# b295_rev0.net
KiCad netlist of a schematic drawn in EAGLE
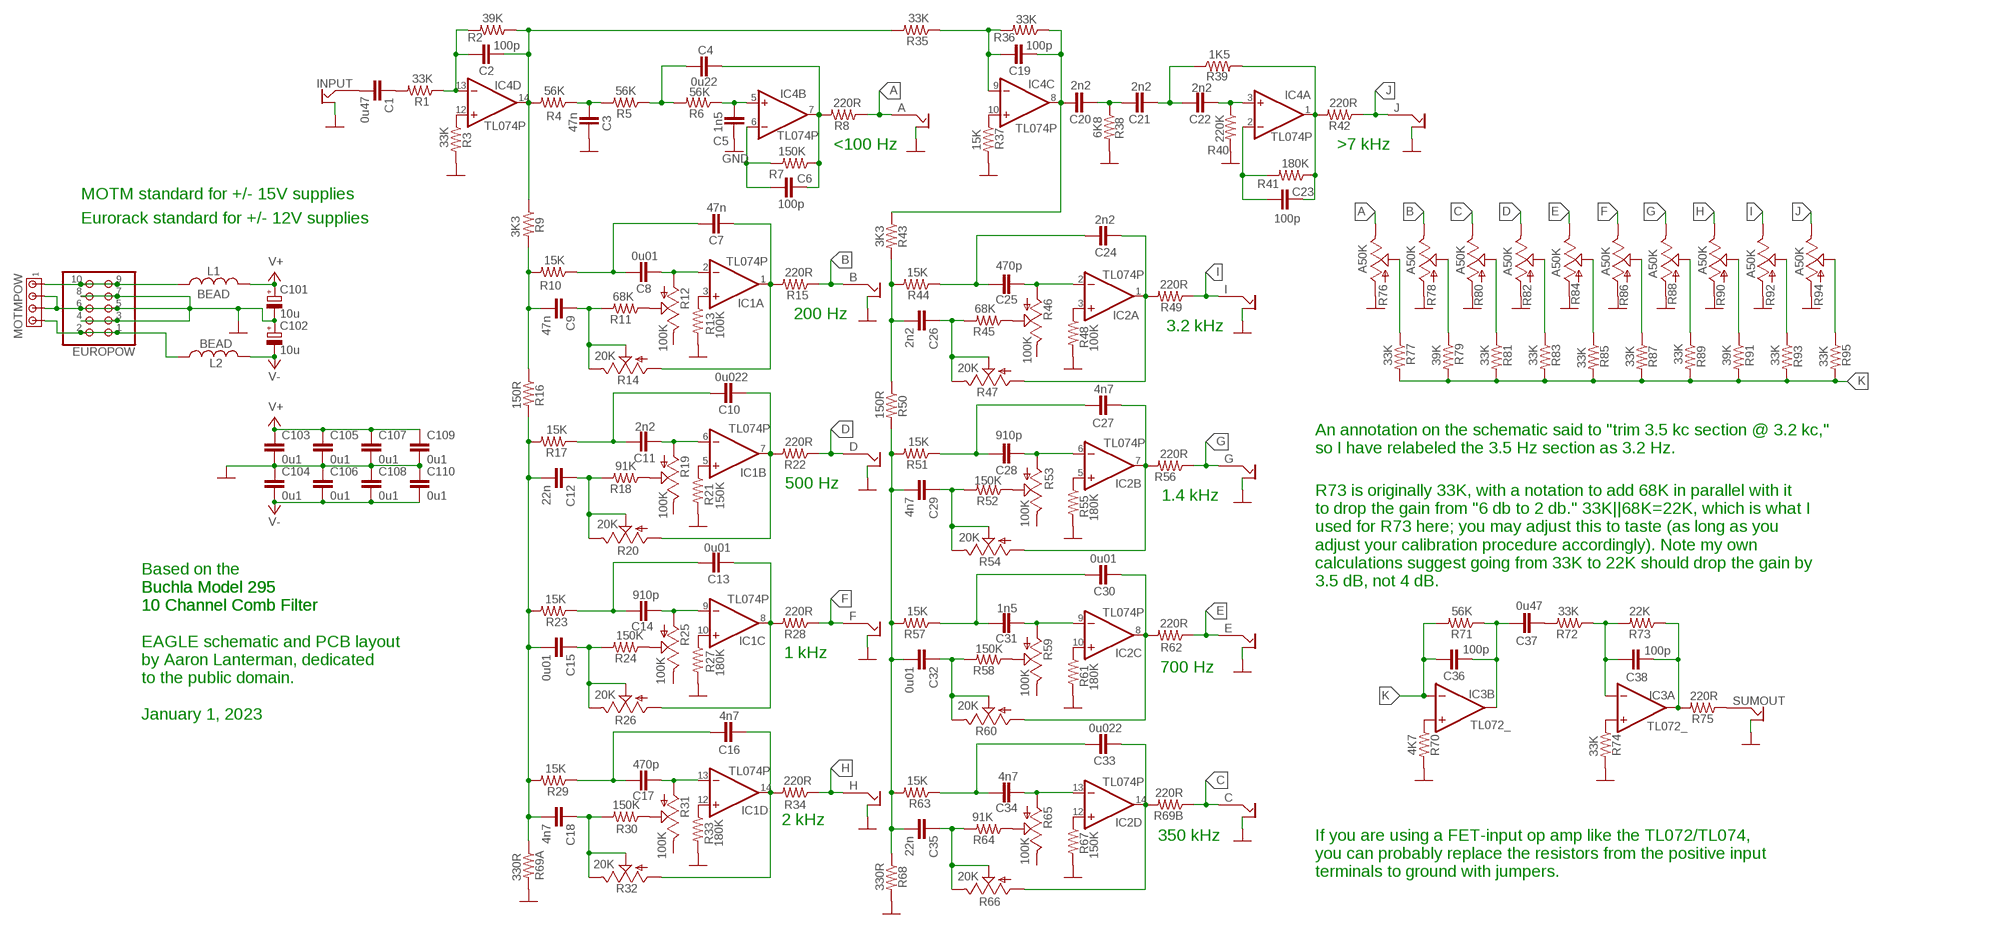
[diagram p0: schematic, sheet 1]

(export (version "E")
  (design (tool "Eeschema 10.0.6"))
  (components
    (comp (ref "A")
      (value "OFFBOARD2JACKALT_AARON")
      (footprint "eagle-import:OFFBOARD2JACKALT")
      (libsource (lib "eagle-import") (part "OFFBOARD2JACKALT_AARON"))
    )
    (comp (ref "B")
      (value "OFFBOARD2JACKALT_AARON")
      (footprint "eagle-import:OFFBOARD2JACKALT")
      (libsource (lib "eagle-import") (part "OFFBOARD2JACKALT_AARON"))
    )
    (comp (ref "C")
      (value "OFFBOARD2JACKALT_AARON")
      (footprint "eagle-import:OFFBOARD2JACKALT")
      (libsource (lib "eagle-import") (part "OFFBOARD2JACKALT_AARON"))
    )
    (comp (ref "C1")
      (value "0u47")
      (footprint "eagle-import:C050-025X075-AARON")
      (libsource (lib "eagle-import") (part "C-EU050-025X075-AARON"))
    )
    (comp (ref "C2")
      (value "100p")
      (footprint "eagle-import:C050-025X075-AARON")
      (libsource (lib "eagle-import") (part "C-EU050-025X075-AARON"))
    )
    (comp (ref "C3")
      (value "47n")
      (footprint "eagle-import:C050-025X075-AARON")
      (libsource (lib "eagle-import") (part "C-EU050-025X075-AARON"))
    )
    (comp (ref "C4")
      (value "0u22")
      (footprint "eagle-import:C050-025X075-AARON")
      (libsource (lib "eagle-import") (part "C-EU050-025X075-AARON"))
    )
    (comp (ref "C5")
      (value "1n5")
      (footprint "eagle-import:C050-025X075-AARON")
      (libsource (lib "eagle-import") (part "C-EU050-025X075-AARON"))
    )
    (comp (ref "C6")
      (value "100p")
      (footprint "eagle-import:C050-025X075-AARON")
      (libsource (lib "eagle-import") (part "C-EU050-025X075-AARON"))
    )
    (comp (ref "C7")
      (value "47n")
      (footprint "eagle-import:C050-025X075-AARON")
      (libsource (lib "eagle-import") (part "C-EU050-025X075-AARON"))
    )
    (comp (ref "C8")
      (value "0u01")
      (footprint "eagle-import:C050-025X075-AARON")
      (libsource (lib "eagle-import") (part "C-EU050-025X075-AARON"))
    )
    (comp (ref "C9")
      (value "47n")
      (footprint "eagle-import:C050-025X075-AARON")
      (libsource (lib "eagle-import") (part "C-EU050-025X075-AARON"))
    )
    (comp (ref "C10")
      (value "0u022")
      (footprint "eagle-import:C050-025X075-AARON")
      (libsource (lib "eagle-import") (part "C-EU050-025X075-AARON"))
    )
    (comp (ref "C11")
      (value "2n2")
      (footprint "eagle-import:C050-025X075-AARON")
      (libsource (lib "eagle-import") (part "C-EU050-025X075-AARON"))
    )
    (comp (ref "C12")
      (value "22n")
      (footprint "eagle-import:C050-025X075-AARON")
      (libsource (lib "eagle-import") (part "C-EU050-025X075-AARON"))
    )
    (comp (ref "C13")
      (value "0u01")
      (footprint "eagle-import:C050-025X075-AARON")
      (libsource (lib "eagle-import") (part "C-EU050-025X075-AARON"))
    )
    (comp (ref "C14")
      (value "910p")
      (footprint "eagle-import:C050-025X075-AARON")
      (libsource (lib "eagle-import") (part "C-EU050-025X075-AARON"))
    )
    (comp (ref "C15")
      (value "0u01")
      (footprint "eagle-import:C050-025X075-AARON")
      (libsource (lib "eagle-import") (part "C-EU050-025X075-AARON"))
    )
    (comp (ref "C16")
      (value "4n7")
      (footprint "eagle-import:C050-025X075-AARON")
      (libsource (lib "eagle-import") (part "C-EU050-025X075-AARON"))
    )
    (comp (ref "C17")
      (value "470p")
      (footprint "eagle-import:C050-025X075-AARON")
      (libsource (lib "eagle-import") (part "C-EU050-025X075-AARON"))
    )
    (comp (ref "C18")
      (value "4n7")
      (footprint "eagle-import:C050-025X075-AARON")
      (libsource (lib "eagle-import") (part "C-EU050-025X075-AARON"))
    )
    (comp (ref "C19")
      (value "100p")
      (footprint "eagle-import:C050-025X075-AARON")
      (libsource (lib "eagle-import") (part "C-EU050-025X075-AARON"))
    )
    (comp (ref "C20")
      (value "2n2")
      (footprint "eagle-import:C050-025X075-AARON")
      (libsource (lib "eagle-import") (part "C-EU050-025X075-AARON"))
    )
    (comp (ref "C21")
      (value "2n2")
      (footprint "eagle-import:C050-025X075-AARON")
      (libsource (lib "eagle-import") (part "C-EU050-025X075-AARON"))
    )
    (comp (ref "C22")
      (value "2n2")
      (footprint "eagle-import:C050-025X075-AARON")
      (libsource (lib "eagle-import") (part "C-EU050-025X075-AARON"))
    )
    (comp (ref "C23")
      (value "100p")
      (footprint "eagle-import:C050-025X075-AARON")
      (libsource (lib "eagle-import") (part "C-EU050-025X075-AARON"))
    )
    (comp (ref "C24")
      (value "2n2")
      (footprint "eagle-import:C050-025X075-AARON")
      (libsource (lib "eagle-import") (part "C-EU050-025X075-AARON"))
    )
    (comp (ref "C25")
      (value "470p")
      (footprint "eagle-import:C050-025X075-AARON")
      (libsource (lib "eagle-import") (part "C-EU050-025X075-AARON"))
    )
    (comp (ref "C26")
      (value "2n2")
      (footprint "eagle-import:C050-025X075-AARON")
      (libsource (lib "eagle-import") (part "C-EU050-025X075-AARON"))
    )
    (comp (ref "C27")
      (value "4n7")
      (footprint "eagle-import:C050-025X075-AARON")
      (libsource (lib "eagle-import") (part "C-EU050-025X075-AARON"))
    )
    (comp (ref "C28")
      (value "910p")
      (footprint "eagle-import:C050-025X075-AARON")
      (libsource (lib "eagle-import") (part "C-EU050-025X075-AARON"))
    )
    (comp (ref "C29")
      (value "4n7")
      (footprint "eagle-import:C050-025X075-AARON")
      (libsource (lib "eagle-import") (part "C-EU050-025X075-AARON"))
    )
    (comp (ref "C30")
      (value "0u01")
      (footprint "eagle-import:C050-025X075-AARON")
      (libsource (lib "eagle-import") (part "C-EU050-025X075-AARON"))
    )
    (comp (ref "C31")
      (value "1n5")
      (footprint "eagle-import:C050-025X075-AARON")
      (libsource (lib "eagle-import") (part "C-EU050-025X075-AARON"))
    )
    (comp (ref "C32")
      (value "0u01")
      (footprint "eagle-import:C050-025X075-AARON")
      (libsource (lib "eagle-import") (part "C-EU050-025X075-AARON"))
    )
    (comp (ref "C33")
      (value "0u022")
      (footprint "eagle-import:C050-025X075-AARON")
      (libsource (lib "eagle-import") (part "C-EU050-025X075-AARON"))
    )
    (comp (ref "C34")
      (value "4n7")
      (footprint "eagle-import:C050-025X075-AARON")
      (libsource (lib "eagle-import") (part "C-EU050-025X075-AARON"))
    )
    (comp (ref "C35")
      (value "22n")
      (footprint "eagle-import:C050-025X075-AARON")
      (libsource (lib "eagle-import") (part "C-EU050-025X075-AARON"))
    )
    (comp (ref "C36")
      (value "100p")
      (footprint "eagle-import:C050-025X075-AARON")
      (libsource (lib "eagle-import") (part "C-EU050-025X075-AARON"))
    )
    (comp (ref "C37")
      (value "0u47")
      (footprint "eagle-import:C050-025X075-AARON")
      (libsource (lib "eagle-import") (part "C-EU050-025X075-AARON"))
    )
    (comp (ref "C38")
      (value "100p")
      (footprint "eagle-import:C050-025X075-AARON")
      (libsource (lib "eagle-import") (part "C-EU050-025X075-AARON"))
    )
    (comp (ref "C101")
      (value "10u")
      (footprint "eagle-import:E1,8-4")
      (libsource (lib "eagle-import") (part "CPOL-EUE1.8-4"))
    )
    (comp (ref "C102")
      (value "10u")
      (footprint "eagle-import:E1,8-4")
      (libsource (lib "eagle-import") (part "CPOL-EUE1.8-4"))
    )
    (comp (ref "C103")
      (value "0u1")
      (footprint "eagle-import:C050-025X075-AARON")
      (libsource (lib "eagle-import") (part "C-EU050-025X075-AARON"))
    )
    (comp (ref "C104")
      (value "0u1")
      (footprint "eagle-import:C050-025X075-AARON")
      (libsource (lib "eagle-import") (part "C-EU050-025X075-AARON"))
    )
    (comp (ref "C105")
      (value "0u1")
      (footprint "eagle-import:C050-025X075-AARON")
      (libsource (lib "eagle-import") (part "C-EU050-025X075-AARON"))
    )
    (comp (ref "C106")
      (value "0u1")
      (footprint "eagle-import:C050-025X075-AARON")
      (libsource (lib "eagle-import") (part "C-EU050-025X075-AARON"))
    )
    (comp (ref "C107")
      (value "0u1")
      (footprint "eagle-import:C050-025X075-AARON")
      (libsource (lib "eagle-import") (part "C-EU050-025X075-AARON"))
    )
    (comp (ref "C108")
      (value "0u1")
      (footprint "eagle-import:C050-025X075-AARON")
      (libsource (lib "eagle-import") (part "C-EU050-025X075-AARON"))
    )
    (comp (ref "C109")
      (value "0u1")
      (footprint "eagle-import:C050-025X075-AARON")
      (libsource (lib "eagle-import") (part "C-EU050-025X075-AARON"))
    )
    (comp (ref "C110")
      (value "0u1")
      (footprint "eagle-import:C050-025X075-AARON")
      (libsource (lib "eagle-import") (part "C-EU050-025X075-AARON"))
    )
    (comp (ref "D")
      (value "OFFBOARD2JACKALT_AARON")
      (footprint "eagle-import:OFFBOARD2JACKALT")
      (libsource (lib "eagle-import") (part "OFFBOARD2JACKALT_AARON"))
    )
    (comp (ref "E")
      (value "OFFBOARD2JACKALT_AARON")
      (footprint "eagle-import:OFFBOARD2JACKALT")
      (libsource (lib "eagle-import") (part "OFFBOARD2JACKALT_AARON"))
    )
    (comp (ref "EUROPOW")
      (value "PINHD-2X5")
      (footprint "eagle-import:2X05")
      (libsource (lib "eagle-import") (part "PINHD-2X5"))
    )
    (comp (ref "F")
      (value "OFFBOARD2JACKALT_AARON")
      (footprint "eagle-import:OFFBOARD2JACKALT")
      (libsource (lib "eagle-import") (part "OFFBOARD2JACKALT_AARON"))
    )
    (comp (ref "G")
      (value "OFFBOARD2JACKALT_AARON")
      (footprint "eagle-import:OFFBOARD2JACKALT")
      (libsource (lib "eagle-import") (part "OFFBOARD2JACKALT_AARON"))
    )
    (comp (ref "H")
      (value "OFFBOARD2JACKALT_AARON")
      (footprint "eagle-import:OFFBOARD2JACKALT")
      (libsource (lib "eagle-import") (part "OFFBOARD2JACKALT_AARON"))
    )
    (comp (ref "I")
      (value "OFFBOARD2JACKALT_AARON")
      (footprint "eagle-import:OFFBOARD2JACKALT")
      (libsource (lib "eagle-import") (part "OFFBOARD2JACKALT_AARON"))
    )
    (comp (ref "IC1")
      (value "TL074P")
      (footprint "eagle-import:DIL14")
      (libsource (lib "eagle-import") (part "TL074P"))
    )
    (comp (ref "IC2")
      (value "TL074P")
      (footprint "eagle-import:DIL14")
      (libsource (lib "eagle-import") (part "TL074P"))
    )
    (comp (ref "IC3")
      (value "TL072_")
      (footprint "eagle-import:DIL08")
      (libsource (lib "eagle-import") (part "TL072_"))
    )
    (comp (ref "IC4")
      (value "TL074P")
      (footprint "eagle-import:DIL14")
      (libsource (lib "eagle-import") (part "TL074P"))
    )
    (comp (ref "INPUT")
      (value "OFFBOARD2JACKALT_AARON")
      (footprint "eagle-import:OFFBOARD2JACKALT")
      (libsource (lib "eagle-import") (part "OFFBOARD2JACKALT_AARON"))
    )
    (comp (ref "J")
      (value "OFFBOARD2JACKALT_AARON")
      (footprint "eagle-import:OFFBOARD2JACKALT")
      (libsource (lib "eagle-import") (part "OFFBOARD2JACKALT_AARON"))
    )
    (comp (ref "L1")
      (value "BEAD")
      (footprint "eagle-import:0207_10")
      (libsource (lib "eagle-import") (part "L-US0207/10"))
    )
    (comp (ref "L2")
      (value "BEAD")
      (footprint "eagle-import:0207_10")
      (libsource (lib "eagle-import") (part "L-US0207/10"))
    )
    (comp (ref "MOTMPOW")
      (value "MTA04-156")
      (footprint "eagle-import:1X4MTA")
      (libsource (lib "eagle-import") (part "MTA04-156"))
    )
    (comp (ref "R1")
      (value "33K")
      (footprint "eagle-import:0207_10")
      (libsource (lib "eagle-import") (part "R-US_0207/10"))
    )
    (comp (ref "R2")
      (value "39K")
      (footprint "eagle-import:0207_10")
      (libsource (lib "eagle-import") (part "R-US_0207/10"))
    )
    (comp (ref "R3")
      (value "33K")
      (footprint "eagle-import:0207_10")
      (libsource (lib "eagle-import") (part "R-US_0207/10"))
    )
    (comp (ref "R4")
      (value "56K")
      (footprint "eagle-import:0207_10")
      (libsource (lib "eagle-import") (part "R-US_0207/10"))
    )
    (comp (ref "R5")
      (value "56K")
      (footprint "eagle-import:0207_10")
      (libsource (lib "eagle-import") (part "R-US_0207/10"))
    )
    (comp (ref "R6")
      (value "56K")
      (footprint "eagle-import:0207_10")
      (libsource (lib "eagle-import") (part "R-US_0207/10"))
    )
    (comp (ref "R7")
      (value "150K")
      (footprint "eagle-import:0207_10")
      (libsource (lib "eagle-import") (part "R-US_0207/10"))
    )
    (comp (ref "R8")
      (value "220R")
      (footprint "eagle-import:0207_10")
      (libsource (lib "eagle-import") (part "R-US_0207/10"))
    )
    (comp (ref "R9")
      (value "3K3")
      (footprint "eagle-import:0207_10")
      (libsource (lib "eagle-import") (part "R-US_0207/10"))
    )
    (comp (ref "R10")
      (value "15K")
      (footprint "eagle-import:0207_10")
      (libsource (lib "eagle-import") (part "R-US_0207/10"))
    )
    (comp (ref "R11")
      (value "68K")
      (footprint "eagle-import:0207_10")
      (libsource (lib "eagle-import") (part "R-US_0207/10"))
    )
    (comp (ref "R12")
      (value "100K")
      (footprint "eagle-import:B64Y")
      (libsource (lib "eagle-import") (part "TRIM_US-B64Y"))
    )
    (comp (ref "R13")
      (value "100K")
      (footprint "eagle-import:0207_10")
      (libsource (lib "eagle-import") (part "R-US_0207/10"))
    )
    (comp (ref "R14")
      (value "20K")
      (footprint "eagle-import:B64Y")
      (libsource (lib "eagle-import") (part "TRIM_US-B64Y"))
    )
    (comp (ref "R15")
      (value "220R")
      (footprint "eagle-import:0207_10")
      (libsource (lib "eagle-import") (part "R-US_0207/10"))
    )
    (comp (ref "R16")
      (value "150R")
      (footprint "eagle-import:0207_10")
      (libsource (lib "eagle-import") (part "R-US_0207/10"))
    )
    (comp (ref "R17")
      (value "15K")
      (footprint "eagle-import:0207_10")
      (libsource (lib "eagle-import") (part "R-US_0207/10"))
    )
    (comp (ref "R18")
      (value "91K")
      (footprint "eagle-import:0207_10")
      (libsource (lib "eagle-import") (part "R-US_0207/10"))
    )
    (comp (ref "R19")
      (value "100K")
      (footprint "eagle-import:B64Y")
      (libsource (lib "eagle-import") (part "TRIM_US-B64Y"))
    )
    (comp (ref "R20")
      (value "20K")
      (footprint "eagle-import:B64Y")
      (libsource (lib "eagle-import") (part "TRIM_US-B64Y"))
    )
    (comp (ref "R21")
      (value "150K")
      (footprint "eagle-import:0207_10")
      (libsource (lib "eagle-import") (part "R-US_0207/10"))
    )
    (comp (ref "R22")
      (value "220R")
      (footprint "eagle-import:0207_10")
      (libsource (lib "eagle-import") (part "R-US_0207/10"))
    )
    (comp (ref "R23")
      (value "15K")
      (footprint "eagle-import:0207_10")
      (libsource (lib "eagle-import") (part "R-US_0207/10"))
    )
    (comp (ref "R24")
      (value "150K")
      (footprint "eagle-import:0207_10")
      (libsource (lib "eagle-import") (part "R-US_0207/10"))
    )
    (comp (ref "R25")
      (value "100K")
      (footprint "eagle-import:B64Y")
      (libsource (lib "eagle-import") (part "TRIM_US-B64Y"))
    )
    (comp (ref "R26")
      (value "20K")
      (footprint "eagle-import:B64Y")
      (libsource (lib "eagle-import") (part "TRIM_US-B64Y"))
    )
    (comp (ref "R27")
      (value "180K")
      (footprint "eagle-import:0207_10")
      (libsource (lib "eagle-import") (part "R-US_0207/10"))
    )
    (comp (ref "R28")
      (value "220R")
      (footprint "eagle-import:0207_10")
      (libsource (lib "eagle-import") (part "R-US_0207/10"))
    )
    (comp (ref "R29")
      (value "15K")
      (footprint "eagle-import:0207_10")
      (libsource (lib "eagle-import") (part "R-US_0207/10"))
    )
    (comp (ref "R30")
      (value "150K")
      (footprint "eagle-import:0207_10")
      (libsource (lib "eagle-import") (part "R-US_0207/10"))
    )
    (comp (ref "R31")
      (value "100K")
      (footprint "eagle-import:B64Y")
      (libsource (lib "eagle-import") (part "TRIM_US-B64Y"))
    )
    (comp (ref "R32")
      (value "20K")
      (footprint "eagle-import:B64Y")
      (libsource (lib "eagle-import") (part "TRIM_US-B64Y"))
    )
    (comp (ref "R33")
      (value "180K")
      (footprint "eagle-import:0207_10")
      (libsource (lib "eagle-import") (part "R-US_0207/10"))
    )
    (comp (ref "R34")
      (value "220R")
      (footprint "eagle-import:0207_10")
      (libsource (lib "eagle-import") (part "R-US_0207/10"))
    )
    (comp (ref "R35")
      (value "33K")
      (footprint "eagle-import:0207_10")
      (libsource (lib "eagle-import") (part "R-US_0207/10"))
    )
    (comp (ref "R36")
      (value "33K")
      (footprint "eagle-import:0207_10")
      (libsource (lib "eagle-import") (part "R-US_0207/10"))
    )
    (comp (ref "R37")
      (value "15K")
      (footprint "eagle-import:0207_10")
      (libsource (lib "eagle-import") (part "R-US_0207/10"))
    )
    (comp (ref "R38")
      (value "6K8")
      (footprint "eagle-import:0207_10")
      (libsource (lib "eagle-import") (part "R-US_0207/10"))
    )
    (comp (ref "R39")
      (value "1K5")
      (footprint "eagle-import:0207_10")
      (libsource (lib "eagle-import") (part "R-US_0207/10"))
    )
    (comp (ref "R40")
      (value "220K")
      (footprint "eagle-import:0207_10")
      (libsource (lib "eagle-import") (part "R-US_0207/10"))
    )
    (comp (ref "R41")
      (value "180K")
      (footprint "eagle-import:0207_10")
      (libsource (lib "eagle-import") (part "R-US_0207/10"))
    )
    (comp (ref "R42")
      (value "220R")
      (footprint "eagle-import:0207_10")
      (libsource (lib "eagle-import") (part "R-US_0207/10"))
    )
    (comp (ref "R43")
      (value "3K3")
      (footprint "eagle-import:0207_10")
      (libsource (lib "eagle-import") (part "R-US_0207/10"))
    )
    (comp (ref "R44")
      (value "15K")
      (footprint "eagle-import:0207_10")
      (libsource (lib "eagle-import") (part "R-US_0207/10"))
    )
    (comp (ref "R45")
      (value "68K")
      (footprint "eagle-import:0207_10")
      (libsource (lib "eagle-import") (part "R-US_0207/10"))
    )
    (comp (ref "R46")
      (value "100K")
      (footprint "eagle-import:B64Y")
      (libsource (lib "eagle-import") (part "TRIM_US-B64Y"))
    )
    (comp (ref "R47")
      (value "20K")
      (footprint "eagle-import:B64Y")
      (libsource (lib "eagle-import") (part "TRIM_US-B64Y"))
    )
    (comp (ref "R48")
      (value "100K")
      (footprint "eagle-import:0207_10")
      (libsource (lib "eagle-import") (part "R-US_0207/10"))
    )
    (comp (ref "R49")
      (value "220R")
      (footprint "eagle-import:0207_10")
      (libsource (lib "eagle-import") (part "R-US_0207/10"))
    )
    (comp (ref "R50")
      (value "150R")
      (footprint "eagle-import:0207_10")
      (libsource (lib "eagle-import") (part "R-US_0207/10"))
    )
    (comp (ref "R51")
      (value "15K")
      (footprint "eagle-import:0207_10")
      (libsource (lib "eagle-import") (part "R-US_0207/10"))
    )
    (comp (ref "R52")
      (value "150K")
      (footprint "eagle-import:0207_10")
      (libsource (lib "eagle-import") (part "R-US_0207/10"))
    )
    (comp (ref "R53")
      (value "100K")
      (footprint "eagle-import:B64Y")
      (libsource (lib "eagle-import") (part "TRIM_US-B64Y"))
    )
    (comp (ref "R54")
      (value "20K")
      (footprint "eagle-import:B64Y")
      (libsource (lib "eagle-import") (part "TRIM_US-B64Y"))
    )
    (comp (ref "R55")
      (value "180K")
      (footprint "eagle-import:0207_10")
      (libsource (lib "eagle-import") (part "R-US_0207/10"))
    )
    (comp (ref "R56")
      (value "220R")
      (footprint "eagle-import:0207_10")
      (libsource (lib "eagle-import") (part "R-US_0207/10"))
    )
    (comp (ref "R57")
      (value "15K")
      (footprint "eagle-import:0207_10")
      (libsource (lib "eagle-import") (part "R-US_0207/10"))
    )
    (comp (ref "R58")
      (value "150K")
      (footprint "eagle-import:0207_10")
      (libsource (lib "eagle-import") (part "R-US_0207/10"))
    )
    (comp (ref "R59")
      (value "100K")
      (footprint "eagle-import:B64Y")
      (libsource (lib "eagle-import") (part "TRIM_US-B64Y"))
    )
    (comp (ref "R60")
      (value "20K")
      (footprint "eagle-import:B64Y")
      (libsource (lib "eagle-import") (part "TRIM_US-B64Y"))
    )
    (comp (ref "R61")
      (value "180K")
      (footprint "eagle-import:0207_10")
      (libsource (lib "eagle-import") (part "R-US_0207/10"))
    )
    (comp (ref "R62")
      (value "220R")
      (footprint "eagle-import:0207_10")
      (libsource (lib "eagle-import") (part "R-US_0207/10"))
    )
    (comp (ref "R63")
      (value "15K")
      (footprint "eagle-import:0207_10")
      (libsource (lib "eagle-import") (part "R-US_0207/10"))
    )
    (comp (ref "R64")
      (value "91K")
      (footprint "eagle-import:0207_10")
      (libsource (lib "eagle-import") (part "R-US_0207/10"))
    )
    (comp (ref "R65")
      (value "100K")
      (footprint "eagle-import:B64Y")
      (libsource (lib "eagle-import") (part "TRIM_US-B64Y"))
    )
    (comp (ref "R66")
      (value "20K")
      (footprint "eagle-import:B64Y")
      (libsource (lib "eagle-import") (part "TRIM_US-B64Y"))
    )
    (comp (ref "R67")
      (value "150K")
      (footprint "eagle-import:0207_10")
      (libsource (lib "eagle-import") (part "R-US_0207/10"))
    )
    (comp (ref "R68")
      (value "330R")
      (footprint "eagle-import:0207_10")
      (libsource (lib "eagle-import") (part "R-US_0207/10"))
    )
    (comp (ref "R69A")
      (value "330R")
      (footprint "eagle-import:0207_10")
      (libsource (lib "eagle-import") (part "R-US_0207/10"))
    )
    (comp (ref "R69B")
      (value "220R")
      (footprint "eagle-import:0207_10")
      (libsource (lib "eagle-import") (part "R-US_0207/10"))
    )
    (comp (ref "R70")
      (value "4K7")
      (footprint "eagle-import:0207_10")
      (libsource (lib "eagle-import") (part "R-US_0207/10"))
    )
    (comp (ref "R71")
      (value "56K")
      (footprint "eagle-import:0207_10")
      (libsource (lib "eagle-import") (part "R-US_0207/10"))
    )
    (comp (ref "R72")
      (value "33K")
      (footprint "eagle-import:0207_10")
      (libsource (lib "eagle-import") (part "R-US_0207/10"))
    )
    (comp (ref "R73")
      (value "22K")
      (footprint "eagle-import:0207_10")
      (libsource (lib "eagle-import") (part "R-US_0207/10"))
    )
    (comp (ref "R74")
      (value "33K")
      (footprint "eagle-import:0207_10")
      (libsource (lib "eagle-import") (part "R-US_0207/10"))
    )
    (comp (ref "R75")
      (value "220R")
      (footprint "eagle-import:0207_10")
      (libsource (lib "eagle-import") (part "R-US_0207/10"))
    )
    (comp (ref "R76")
      (value "A50K")
      (footprint "eagle-import:B64Y")
      (libsource (lib "eagle-import") (part "TRIM_US-B64Y"))
    )
    (comp (ref "R77")
      (value "33K")
      (footprint "eagle-import:0207_10")
      (libsource (lib "eagle-import") (part "R-US_0207/10"))
    )
    (comp (ref "R78")
      (value "A50K")
      (footprint "eagle-import:B64Y")
      (libsource (lib "eagle-import") (part "TRIM_US-B64Y"))
    )
    (comp (ref "R79")
      (value "39K")
      (footprint "eagle-import:0207_10")
      (libsource (lib "eagle-import") (part "R-US_0207/10"))
    )
    (comp (ref "R80")
      (value "A50K")
      (footprint "eagle-import:B64Y")
      (libsource (lib "eagle-import") (part "TRIM_US-B64Y"))
    )
    (comp (ref "R81")
      (value "33K")
      (footprint "eagle-import:0207_10")
      (libsource (lib "eagle-import") (part "R-US_0207/10"))
    )
    (comp (ref "R82")
      (value "A50K")
      (footprint "eagle-import:B64Y")
      (libsource (lib "eagle-import") (part "TRIM_US-B64Y"))
    )
    (comp (ref "R83")
      (value "33K")
      (footprint "eagle-import:0207_10")
      (libsource (lib "eagle-import") (part "R-US_0207/10"))
    )
    (comp (ref "R84")
      (value "A50K")
      (footprint "eagle-import:B64Y")
      (libsource (lib "eagle-import") (part "TRIM_US-B64Y"))
    )
    (comp (ref "R85")
      (value "33K")
      (footprint "eagle-import:0207_10")
      (libsource (lib "eagle-import") (part "R-US_0207/10"))
    )
    (comp (ref "R86")
      (value "A50K")
      (footprint "eagle-import:B64Y")
      (libsource (lib "eagle-import") (part "TRIM_US-B64Y"))
    )
    (comp (ref "R87")
      (value "33K")
      (footprint "eagle-import:0207_10")
      (libsource (lib "eagle-import") (part "R-US_0207/10"))
    )
    (comp (ref "R88")
      (value "A50K")
      (footprint "eagle-import:B64Y")
      (libsource (lib "eagle-import") (part "TRIM_US-B64Y"))
    )
    (comp (ref "R89")
      (value "33K")
      (footprint "eagle-import:0207_10")
      (libsource (lib "eagle-import") (part "R-US_0207/10"))
    )
    (comp (ref "R90")
      (value "A50K")
      (footprint "eagle-import:B64Y")
      (libsource (lib "eagle-import") (part "TRIM_US-B64Y"))
    )
    (comp (ref "R91")
      (value "39K")
      (footprint "eagle-import:0207_10")
      (libsource (lib "eagle-import") (part "R-US_0207/10"))
    )
    (comp (ref "R92")
      (value "A50K")
      (footprint "eagle-import:B64Y")
      (libsource (lib "eagle-import") (part "TRIM_US-B64Y"))
    )
    (comp (ref "R93")
      (value "33K")
      (footprint "eagle-import:0207_10")
      (libsource (lib "eagle-import") (part "R-US_0207/10"))
    )
    (comp (ref "R94")
      (value "A50K")
      (footprint "eagle-import:B64Y")
      (libsource (lib "eagle-import") (part "TRIM_US-B64Y"))
    )
    (comp (ref "R95")
      (value "33K")
      (footprint "eagle-import:0207_10")
      (libsource (lib "eagle-import") (part "R-US_0207/10"))
    )
    (comp (ref "SUMOUT")
      (value "OFFBOARD2JACKALT_AARON")
      (footprint "eagle-import:OFFBOARD2JACKALT")
      (libsource (lib "eagle-import") (part "OFFBOARD2JACKALT_AARON"))
    )
  )
  (nets
    (net (code "1") (name "A") (class "Default")
      (node (ref "A") (pin "SIGNAL") (pinfunction "SIGNAL_SIGNAL") (pintype "passive"))
      (node (ref "R76") (pin "E") (pinfunction "E_E") (pintype "passive"))
      (node (ref "R8") (pin "1") (pinfunction "1_1") (pintype "passive"))
    )
    (net (code "2") (name "B") (class "Default")
      (node (ref "B") (pin "SIGNAL") (pinfunction "SIGNAL_SIGNAL") (pintype "passive"))
      (node (ref "R15") (pin "1") (pinfunction "1_1") (pintype "passive"))
      (node (ref "R78") (pin "E") (pinfunction "E_E") (pintype "passive"))
    )
    (net (code "3") (name "C") (class "Default")
      (node (ref "C") (pin "SIGNAL") (pinfunction "SIGNAL_SIGNAL") (pintype "passive"))
      (node (ref "R69B") (pin "1") (pinfunction "1_1") (pintype "passive"))
      (node (ref "R80") (pin "E") (pinfunction "E_E") (pintype "passive"))
    )
    (net (code "4") (name "D") (class "Default")
      (node (ref "D") (pin "SIGNAL") (pinfunction "SIGNAL_SIGNAL") (pintype "passive"))
      (node (ref "R22") (pin "1") (pinfunction "1_1") (pintype "passive"))
      (node (ref "R82") (pin "E") (pinfunction "E_E") (pintype "passive"))
    )
    (net (code "5") (name "E") (class "Default")
      (node (ref "E") (pin "SIGNAL") (pinfunction "SIGNAL_SIGNAL") (pintype "passive"))
      (node (ref "R62") (pin "1") (pinfunction "1_1") (pintype "passive"))
      (node (ref "R84") (pin "E") (pinfunction "E_E") (pintype "passive"))
    )
    (net (code "6") (name "F") (class "Default")
      (node (ref "F") (pin "SIGNAL") (pinfunction "SIGNAL_SIGNAL") (pintype "passive"))
      (node (ref "R28") (pin "1") (pinfunction "1_1") (pintype "passive"))
      (node (ref "R86") (pin "E") (pinfunction "E_E") (pintype "passive"))
    )
    (net (code "7") (name "G") (class "Default")
      (node (ref "G") (pin "SIGNAL") (pinfunction "SIGNAL_SIGNAL") (pintype "passive"))
      (node (ref "R56") (pin "1") (pinfunction "1_1") (pintype "passive"))
      (node (ref "R88") (pin "E") (pinfunction "E_E") (pintype "passive"))
    )
    (net (code "8") (name "GND") (class "Default")
      (node (ref "A") (pin "GND") (pinfunction "GND_GND") (pintype "passive"))
      (node (ref "B") (pin "GND") (pinfunction "GND_GND") (pintype "passive"))
      (node (ref "C") (pin "GND") (pinfunction "GND_GND") (pintype "passive"))
      (node (ref "C101") (pin "-") (pinfunction "-_-") (pintype "passive"))
      (node (ref "C102") (pin "+") (pinfunction "+_+") (pintype "passive"))
      (node (ref "C103") (pin "2") (pinfunction "2_2") (pintype "passive"))
      (node (ref "C104") (pin "1") (pinfunction "1_1") (pintype "passive"))
      (node (ref "C105") (pin "2") (pinfunction "2_2") (pintype "passive"))
      (node (ref "C106") (pin "1") (pinfunction "1_1") (pintype "passive"))
      (node (ref "C107") (pin "2") (pinfunction "2_2") (pintype "passive"))
      (node (ref "C108") (pin "1") (pinfunction "1_1") (pintype "passive"))
      (node (ref "C109") (pin "2") (pinfunction "2_2") (pintype "passive"))
      (node (ref "C110") (pin "1") (pinfunction "1_1") (pintype "passive"))
      (node (ref "C3") (pin "1") (pinfunction "1_1") (pintype "passive"))
      (node (ref "C5") (pin "1") (pinfunction "1_1") (pintype "passive"))
      (node (ref "D") (pin "GND") (pinfunction "GND_GND") (pintype "passive"))
      (node (ref "E") (pin "GND") (pinfunction "GND_GND") (pintype "passive"))
      (node (ref "EUROPOW") (pin "3") (pinfunction "3_3") (pintype "passive"))
      (node (ref "EUROPOW") (pin "4") (pinfunction "4_4") (pintype "passive"))
      (node (ref "EUROPOW") (pin "5") (pinfunction "5_5") (pintype "passive"))
      (node (ref "EUROPOW") (pin "6") (pinfunction "6_6") (pintype "passive"))
      (node (ref "EUROPOW") (pin "7") (pinfunction "7_7") (pintype "passive"))
      (node (ref "EUROPOW") (pin "8") (pinfunction "8_8") (pintype "passive"))
      (node (ref "F") (pin "GND") (pinfunction "GND_GND") (pintype "passive"))
      (node (ref "G") (pin "GND") (pinfunction "GND_GND") (pintype "passive"))
      (node (ref "H") (pin "GND") (pinfunction "GND_GND") (pintype "passive"))
      (node (ref "I") (pin "GND") (pinfunction "GND_GND") (pintype "passive"))
      (node (ref "INPUT") (pin "GND") (pinfunction "GND_GND") (pintype "passive"))
      (node (ref "J") (pin "GND") (pinfunction "GND_GND") (pintype "passive"))
      (node (ref "MOTMPOW") (pin "2") (pinfunction "2_2") (pintype "passive"))
      (node (ref "MOTMPOW") (pin "3") (pinfunction "3_3") (pintype "passive"))
      (node (ref "R13") (pin "2") (pinfunction "2_2") (pintype "passive"))
      (node (ref "R21") (pin "2") (pinfunction "2_2") (pintype "passive"))
      (node (ref "R27") (pin "2") (pinfunction "2_2") (pintype "passive"))
      (node (ref "R3") (pin "2") (pinfunction "2_2") (pintype "passive"))
      (node (ref "R33") (pin "2") (pinfunction "2_2") (pintype "passive"))
      (node (ref "R37") (pin "2") (pinfunction "2_2") (pintype "passive"))
      (node (ref "R38") (pin "2") (pinfunction "2_2") (pintype "passive"))
      (node (ref "R40") (pin "2") (pinfunction "2_2") (pintype "passive"))
      (node (ref "R48") (pin "2") (pinfunction "2_2") (pintype "passive"))
      (node (ref "R55") (pin "2") (pinfunction "2_2") (pintype "passive"))
      (node (ref "R61") (pin "2") (pinfunction "2_2") (pintype "passive"))
      (node (ref "R67") (pin "2") (pinfunction "2_2") (pintype "passive"))
      (node (ref "R68") (pin "2") (pinfunction "2_2") (pintype "passive"))
      (node (ref "R69A") (pin "2") (pinfunction "2_2") (pintype "passive"))
      (node (ref "R70") (pin "2") (pinfunction "2_2") (pintype "passive"))
      (node (ref "R74") (pin "2") (pinfunction "2_2") (pintype "passive"))
      (node (ref "R76") (pin "A") (pinfunction "A_A") (pintype "passive"))
      (node (ref "R78") (pin "A") (pinfunction "A_A") (pintype "passive"))
      (node (ref "R80") (pin "A") (pinfunction "A_A") (pintype "passive"))
      (node (ref "R82") (pin "A") (pinfunction "A_A") (pintype "passive"))
      (node (ref "R84") (pin "A") (pinfunction "A_A") (pintype "passive"))
      (node (ref "R86") (pin "A") (pinfunction "A_A") (pintype "passive"))
      (node (ref "R88") (pin "A") (pinfunction "A_A") (pintype "passive"))
      (node (ref "R90") (pin "A") (pinfunction "A_A") (pintype "passive"))
      (node (ref "R92") (pin "A") (pinfunction "A_A") (pintype "passive"))
      (node (ref "R94") (pin "A") (pinfunction "A_A") (pintype "passive"))
      (node (ref "SUMOUT") (pin "GND") (pinfunction "GND_GND") (pintype "passive"))
    )
    (net (code "9") (name "H") (class "Default")
      (node (ref "H") (pin "SIGNAL") (pinfunction "SIGNAL_SIGNAL") (pintype "passive"))
      (node (ref "R34") (pin "1") (pinfunction "1_1") (pintype "passive"))
      (node (ref "R90") (pin "E") (pinfunction "E_E") (pintype "passive"))
    )
    (net (code "10") (name "I") (class "Default")
      (node (ref "I") (pin "SIGNAL") (pinfunction "SIGNAL_SIGNAL") (pintype "passive"))
      (node (ref "R49") (pin "1") (pinfunction "1_1") (pintype "passive"))
      (node (ref "R92") (pin "E") (pinfunction "E_E") (pintype "passive"))
    )
    (net (code "11") (name "J") (class "Default")
      (node (ref "J") (pin "SIGNAL") (pinfunction "SIGNAL_SIGNAL") (pintype "passive"))
      (node (ref "R42") (pin "1") (pinfunction "1_1") (pintype "passive"))
      (node (ref "R94") (pin "E") (pinfunction "E_E") (pintype "passive"))
    )
    (net (code "12") (name "K") (class "Default")
      (node (ref "C36") (pin "2") (pinfunction "2_2") (pintype "passive"))
      (node (ref "IC3") (pin "6") (pinfunction "-IN_6") (pintype "input"))
      (node (ref "R71") (pin "2") (pinfunction "2_2") (pintype "passive"))
      (node (ref "R77") (pin "2") (pinfunction "2_2") (pintype "passive"))
      (node (ref "R79") (pin "2") (pinfunction "2_2") (pintype "passive"))
      (node (ref "R81") (pin "2") (pinfunction "2_2") (pintype "passive"))
      (node (ref "R83") (pin "2") (pinfunction "2_2") (pintype "passive"))
      (node (ref "R85") (pin "2") (pinfunction "2_2") (pintype "passive"))
      (node (ref "R87") (pin "2") (pinfunction "2_2") (pintype "passive"))
      (node (ref "R89") (pin "2") (pinfunction "2_2") (pintype "passive"))
      (node (ref "R91") (pin "2") (pinfunction "2_2") (pintype "passive"))
      (node (ref "R93") (pin "2") (pinfunction "2_2") (pintype "passive"))
      (node (ref "R95") (pin "2") (pinfunction "2_2") (pintype "passive"))
    )
    (net (code "13") (name "Net-(C1-Pad1)") (class "Default")
      (node (ref "C1") (pin "1") (pinfunction "1_1") (pintype "passive"))
      (node (ref "R1") (pin "2") (pinfunction "2_2") (pintype "passive"))
    )
    (net (code "14") (name "Net-(C1-Pad2)") (class "Default")
      (node (ref "C1") (pin "2") (pinfunction "2_2") (pintype "passive"))
      (node (ref "INPUT") (pin "SIGNAL") (pinfunction "SIGNAL_SIGNAL") (pintype "passive"))
    )
    (net (code "15") (name "Net-(C3-Pad2)") (class "Default")
      (node (ref "C3") (pin "2") (pinfunction "2_2") (pintype "passive"))
      (node (ref "R4") (pin "1") (pinfunction "1_1") (pintype "passive"))
      (node (ref "R5") (pin "2") (pinfunction "2_2") (pintype "passive"))
    )
    (net (code "16") (name "Net-(C4-Pad2)") (class "Default")
      (node (ref "C4") (pin "2") (pinfunction "2_2") (pintype "passive"))
      (node (ref "R5") (pin "1") (pinfunction "1_1") (pintype "passive"))
      (node (ref "R6") (pin "2") (pinfunction "2_2") (pintype "passive"))
    )
    (net (code "17") (name "Net-(C7-Pad2)") (class "Default")
      (node (ref "C7") (pin "2") (pinfunction "2_2") (pintype "passive"))
      (node (ref "C8") (pin "2") (pinfunction "2_2") (pintype "passive"))
      (node (ref "R10") (pin "1") (pinfunction "1_1") (pintype "passive"))
    )
    (net (code "18") (name "Net-(C9-Pad1)") (class "Default")
      (node (ref "C9") (pin "1") (pinfunction "1_1") (pintype "passive"))
      (node (ref "R11") (pin "2") (pinfunction "2_2") (pintype "passive"))
      (node (ref "R14") (pin "E") (pinfunction "E_E") (pintype "passive"))
      (node (ref "R14") (pin "S") (pinfunction "S_S") (pintype "passive"))
    )
    (net (code "19") (name "Net-(C9-Pad2)") (class "Default")
      (node (ref "C9") (pin "2") (pinfunction "2_2") (pintype "passive"))
      (node (ref "R10") (pin "2") (pinfunction "2_2") (pintype "passive"))
      (node (ref "R16") (pin "1") (pinfunction "1_1") (pintype "passive"))
      (node (ref "R9") (pin "2") (pinfunction "2_2") (pintype "passive"))
    )
    (net (code "20") (name "Net-(C10-Pad2)") (class "Default")
      (node (ref "C10") (pin "2") (pinfunction "2_2") (pintype "passive"))
      (node (ref "C11") (pin "2") (pinfunction "2_2") (pintype "passive"))
      (node (ref "R17") (pin "1") (pinfunction "1_1") (pintype "passive"))
    )
    (net (code "21") (name "Net-(C12-Pad1)") (class "Default")
      (node (ref "C12") (pin "1") (pinfunction "1_1") (pintype "passive"))
      (node (ref "R18") (pin "2") (pinfunction "2_2") (pintype "passive"))
      (node (ref "R20") (pin "E") (pinfunction "E_E") (pintype "passive"))
      (node (ref "R20") (pin "S") (pinfunction "S_S") (pintype "passive"))
    )
    (net (code "22") (name "Net-(C12-Pad2)") (class "Default")
      (node (ref "C12") (pin "2") (pinfunction "2_2") (pintype "passive"))
      (node (ref "C15") (pin "2") (pinfunction "2_2") (pintype "passive"))
      (node (ref "C18") (pin "2") (pinfunction "2_2") (pintype "passive"))
      (node (ref "R16") (pin "2") (pinfunction "2_2") (pintype "passive"))
      (node (ref "R17") (pin "2") (pinfunction "2_2") (pintype "passive"))
      (node (ref "R23") (pin "2") (pinfunction "2_2") (pintype "passive"))
      (node (ref "R29") (pin "2") (pinfunction "2_2") (pintype "passive"))
      (node (ref "R69A") (pin "1") (pinfunction "1_1") (pintype "passive"))
    )
    (net (code "23") (name "Net-(C13-Pad2)") (class "Default")
      (node (ref "C13") (pin "2") (pinfunction "2_2") (pintype "passive"))
      (node (ref "C14") (pin "2") (pinfunction "2_2") (pintype "passive"))
      (node (ref "R23") (pin "1") (pinfunction "1_1") (pintype "passive"))
    )
    (net (code "24") (name "Net-(C15-Pad1)") (class "Default")
      (node (ref "C15") (pin "1") (pinfunction "1_1") (pintype "passive"))
      (node (ref "R24") (pin "2") (pinfunction "2_2") (pintype "passive"))
      (node (ref "R26") (pin "E") (pinfunction "E_E") (pintype "passive"))
      (node (ref "R26") (pin "S") (pinfunction "S_S") (pintype "passive"))
    )
    (net (code "25") (name "Net-(C16-Pad2)") (class "Default")
      (node (ref "C16") (pin "2") (pinfunction "2_2") (pintype "passive"))
      (node (ref "C17") (pin "2") (pinfunction "2_2") (pintype "passive"))
      (node (ref "R29") (pin "1") (pinfunction "1_1") (pintype "passive"))
    )
    (net (code "26") (name "Net-(C18-Pad1)") (class "Default")
      (node (ref "C18") (pin "1") (pinfunction "1_1") (pintype "passive"))
      (node (ref "R30") (pin "2") (pinfunction "2_2") (pintype "passive"))
      (node (ref "R32") (pin "E") (pinfunction "E_E") (pintype "passive"))
      (node (ref "R32") (pin "S") (pinfunction "S_S") (pintype "passive"))
    )
    (net (code "27") (name "Net-(C20-Pad1)") (class "Default")
      (node (ref "C20") (pin "1") (pinfunction "1_1") (pintype "passive"))
      (node (ref "C21") (pin "2") (pinfunction "2_2") (pintype "passive"))
      (node (ref "R38") (pin "1") (pinfunction "1_1") (pintype "passive"))
    )
    (net (code "28") (name "Net-(C21-Pad1)") (class "Default")
      (node (ref "C21") (pin "1") (pinfunction "1_1") (pintype "passive"))
      (node (ref "C22") (pin "2") (pinfunction "2_2") (pintype "passive"))
      (node (ref "R39") (pin "1") (pinfunction "1_1") (pintype "passive"))
    )
    (net (code "29") (name "Net-(C24-Pad2)") (class "Default")
      (node (ref "C24") (pin "2") (pinfunction "2_2") (pintype "passive"))
      (node (ref "C25") (pin "2") (pinfunction "2_2") (pintype "passive"))
      (node (ref "R44") (pin "1") (pinfunction "1_1") (pintype "passive"))
    )
    (net (code "30") (name "Net-(C26-Pad1)") (class "Default")
      (node (ref "C26") (pin "1") (pinfunction "1_1") (pintype "passive"))
      (node (ref "R45") (pin "2") (pinfunction "2_2") (pintype "passive"))
      (node (ref "R47") (pin "E") (pinfunction "E_E") (pintype "passive"))
      (node (ref "R47") (pin "S") (pinfunction "S_S") (pintype "passive"))
    )
    (net (code "31") (name "Net-(C26-Pad2)") (class "Default")
      (node (ref "C26") (pin "2") (pinfunction "2_2") (pintype "passive"))
      (node (ref "R43") (pin "2") (pinfunction "2_2") (pintype "passive"))
      (node (ref "R44") (pin "2") (pinfunction "2_2") (pintype "passive"))
      (node (ref "R50") (pin "1") (pinfunction "1_1") (pintype "passive"))
    )
    (net (code "32") (name "Net-(C27-Pad2)") (class "Default")
      (node (ref "C27") (pin "2") (pinfunction "2_2") (pintype "passive"))
      (node (ref "C28") (pin "2") (pinfunction "2_2") (pintype "passive"))
      (node (ref "R51") (pin "1") (pinfunction "1_1") (pintype "passive"))
    )
    (net (code "33") (name "Net-(C29-Pad1)") (class "Default")
      (node (ref "C29") (pin "1") (pinfunction "1_1") (pintype "passive"))
      (node (ref "R52") (pin "2") (pinfunction "2_2") (pintype "passive"))
      (node (ref "R54") (pin "E") (pinfunction "E_E") (pintype "passive"))
      (node (ref "R54") (pin "S") (pinfunction "S_S") (pintype "passive"))
    )
    (net (code "34") (name "Net-(C29-Pad2)") (class "Default")
      (node (ref "C29") (pin "2") (pinfunction "2_2") (pintype "passive"))
      (node (ref "C32") (pin "2") (pinfunction "2_2") (pintype "passive"))
      (node (ref "C35") (pin "2") (pinfunction "2_2") (pintype "passive"))
      (node (ref "R50") (pin "2") (pinfunction "2_2") (pintype "passive"))
      (node (ref "R51") (pin "2") (pinfunction "2_2") (pintype "passive"))
      (node (ref "R57") (pin "2") (pinfunction "2_2") (pintype "passive"))
      (node (ref "R63") (pin "2") (pinfunction "2_2") (pintype "passive"))
      (node (ref "R68") (pin "1") (pinfunction "1_1") (pintype "passive"))
    )
    (net (code "35") (name "Net-(C30-Pad2)") (class "Default")
      (node (ref "C30") (pin "2") (pinfunction "2_2") (pintype "passive"))
      (node (ref "C31") (pin "2") (pinfunction "2_2") (pintype "passive"))
      (node (ref "R57") (pin "1") (pinfunction "1_1") (pintype "passive"))
    )
    (net (code "36") (name "Net-(C32-Pad1)") (class "Default")
      (node (ref "C32") (pin "1") (pinfunction "1_1") (pintype "passive"))
      (node (ref "R58") (pin "2") (pinfunction "2_2") (pintype "passive"))
      (node (ref "R60") (pin "E") (pinfunction "E_E") (pintype "passive"))
      (node (ref "R60") (pin "S") (pinfunction "S_S") (pintype "passive"))
    )
    (net (code "37") (name "Net-(C33-Pad2)") (class "Default")
      (node (ref "C33") (pin "2") (pinfunction "2_2") (pintype "passive"))
      (node (ref "C34") (pin "2") (pinfunction "2_2") (pintype "passive"))
      (node (ref "R63") (pin "1") (pinfunction "1_1") (pintype "passive"))
    )
    (net (code "38") (name "Net-(C35-Pad1)") (class "Default")
      (node (ref "C35") (pin "1") (pinfunction "1_1") (pintype "passive"))
      (node (ref "R64") (pin "2") (pinfunction "2_2") (pintype "passive"))
      (node (ref "R66") (pin "E") (pinfunction "E_E") (pintype "passive"))
      (node (ref "R66") (pin "S") (pinfunction "S_S") (pintype "passive"))
    )
    (net (code "39") (name "Net-(C37-Pad1)") (class "Default")
      (node (ref "C37") (pin "1") (pinfunction "1_1") (pintype "passive"))
      (node (ref "R72") (pin "2") (pinfunction "2_2") (pintype "passive"))
    )
    (net (code "40") (name "Net-(EUROPOW-Pad1)") (class "Default")
      (node (ref "EUROPOW") (pin "1") (pinfunction "1_1") (pintype "passive"))
      (node (ref "EUROPOW") (pin "2") (pinfunction "2_2") (pintype "passive"))
      (node (ref "L2") (pin "1") (pinfunction "1_1") (pintype "passive"))
      (node (ref "MOTMPOW") (pin "4") (pinfunction "4_4") (pintype "passive"))
    )
    (net (code "41") (name "Net-(EUROPOW-Pad10)") (class "Default")
      (node (ref "EUROPOW") (pin "10") (pinfunction "10_10") (pintype "passive"))
      (node (ref "EUROPOW") (pin "9") (pinfunction "9_9") (pintype "passive"))
      (node (ref "L1") (pin "1") (pinfunction "1_1") (pintype "passive"))
      (node (ref "MOTMPOW") (pin "1") (pinfunction "1_1") (pintype "passive"))
    )
    (net (code "42") (name "Net-(IC1A-+IN)") (class "Default")
      (node (ref "IC1") (pin "3") (pinfunction "+IN_3") (pintype "input"))
      (node (ref "R13") (pin "1") (pinfunction "1_1") (pintype "passive"))
    )
    (net (code "43") (name "Net-(IC1A--IN)") (class "Default")
      (node (ref "C8") (pin "1") (pinfunction "1_1") (pintype "passive"))
      (node (ref "IC1") (pin "2") (pinfunction "-IN_2") (pintype "input"))
      (node (ref "R12") (pin "A") (pinfunction "A_A") (pintype "passive"))
    )
    (net (code "44") (name "Net-(IC1A-OUT)") (class "Default")
      (node (ref "C7") (pin "1") (pinfunction "1_1") (pintype "passive"))
      (node (ref "IC1") (pin "1") (pinfunction "OUT_1") (pintype "output"))
      (node (ref "R14") (pin "A") (pinfunction "A_A") (pintype "passive"))
      (node (ref "R15") (pin "2") (pinfunction "2_2") (pintype "passive"))
    )
    (net (code "45") (name "Net-(IC1B-+IN)") (class "Default")
      (node (ref "IC1") (pin "5") (pinfunction "+IN_5") (pintype "input"))
      (node (ref "R21") (pin "1") (pinfunction "1_1") (pintype "passive"))
    )
    (net (code "46") (name "Net-(IC1B--IN)") (class "Default")
      (node (ref "C11") (pin "1") (pinfunction "1_1") (pintype "passive"))
      (node (ref "IC1") (pin "6") (pinfunction "-IN_6") (pintype "input"))
      (node (ref "R19") (pin "A") (pinfunction "A_A") (pintype "passive"))
    )
    (net (code "47") (name "Net-(IC1B-OUT)") (class "Default")
      (node (ref "C10") (pin "1") (pinfunction "1_1") (pintype "passive"))
      (node (ref "IC1") (pin "7") (pinfunction "OUT_7") (pintype "output"))
      (node (ref "R20") (pin "A") (pinfunction "A_A") (pintype "passive"))
      (node (ref "R22") (pin "2") (pinfunction "2_2") (pintype "passive"))
    )
    (net (code "48") (name "Net-(IC1C-+IN)") (class "Default")
      (node (ref "IC1") (pin "10") (pinfunction "+IN_10") (pintype "input"))
      (node (ref "R27") (pin "1") (pinfunction "1_1") (pintype "passive"))
    )
    (net (code "49") (name "Net-(IC1C--IN)") (class "Default")
      (node (ref "C14") (pin "1") (pinfunction "1_1") (pintype "passive"))
      (node (ref "IC1") (pin "9") (pinfunction "-IN_9") (pintype "input"))
      (node (ref "R25") (pin "A") (pinfunction "A_A") (pintype "passive"))
    )
    (net (code "50") (name "Net-(IC1C-OUT)") (class "Default")
      (node (ref "C13") (pin "1") (pinfunction "1_1") (pintype "passive"))
      (node (ref "IC1") (pin "8") (pinfunction "OUT_8") (pintype "output"))
      (node (ref "R26") (pin "A") (pinfunction "A_A") (pintype "passive"))
      (node (ref "R28") (pin "2") (pinfunction "2_2") (pintype "passive"))
    )
    (net (code "51") (name "Net-(IC1D-+IN)") (class "Default")
      (node (ref "IC1") (pin "12") (pinfunction "+IN_12") (pintype "input"))
      (node (ref "R33") (pin "1") (pinfunction "1_1") (pintype "passive"))
    )
    (net (code "52") (name "Net-(IC1D--IN)") (class "Default")
      (node (ref "C17") (pin "1") (pinfunction "1_1") (pintype "passive"))
      (node (ref "IC1") (pin "13") (pinfunction "-IN_13") (pintype "input"))
      (node (ref "R31") (pin "A") (pinfunction "A_A") (pintype "passive"))
    )
    (net (code "53") (name "Net-(IC1D-OUT)") (class "Default")
      (node (ref "C16") (pin "1") (pinfunction "1_1") (pintype "passive"))
      (node (ref "IC1") (pin "14") (pinfunction "OUT_14") (pintype "output"))
      (node (ref "R32") (pin "A") (pinfunction "A_A") (pintype "passive"))
      (node (ref "R34") (pin "2") (pinfunction "2_2") (pintype "passive"))
    )
    (net (code "54") (name "Net-(IC2A-+IN)") (class "Default")
      (node (ref "IC2") (pin "3") (pinfunction "+IN_3") (pintype "input"))
      (node (ref "R48") (pin "1") (pinfunction "1_1") (pintype "passive"))
    )
    (net (code "55") (name "Net-(IC2A--IN)") (class "Default")
      (node (ref "C25") (pin "1") (pinfunction "1_1") (pintype "passive"))
      (node (ref "IC2") (pin "2") (pinfunction "-IN_2") (pintype "input"))
      (node (ref "R46") (pin "A") (pinfunction "A_A") (pintype "passive"))
    )
    (net (code "56") (name "Net-(IC2A-OUT)") (class "Default")
      (node (ref "C24") (pin "1") (pinfunction "1_1") (pintype "passive"))
      (node (ref "IC2") (pin "1") (pinfunction "OUT_1") (pintype "output"))
      (node (ref "R47") (pin "A") (pinfunction "A_A") (pintype "passive"))
      (node (ref "R49") (pin "2") (pinfunction "2_2") (pintype "passive"))
    )
    (net (code "57") (name "Net-(IC2B-+IN)") (class "Default")
      (node (ref "IC2") (pin "5") (pinfunction "+IN_5") (pintype "input"))
      (node (ref "R55") (pin "1") (pinfunction "1_1") (pintype "passive"))
    )
    (net (code "58") (name "Net-(IC2B--IN)") (class "Default")
      (node (ref "C28") (pin "1") (pinfunction "1_1") (pintype "passive"))
      (node (ref "IC2") (pin "6") (pinfunction "-IN_6") (pintype "input"))
      (node (ref "R53") (pin "A") (pinfunction "A_A") (pintype "passive"))
    )
    (net (code "59") (name "Net-(IC2B-OUT)") (class "Default")
      (node (ref "C27") (pin "1") (pinfunction "1_1") (pintype "passive"))
      (node (ref "IC2") (pin "7") (pinfunction "OUT_7") (pintype "output"))
      (node (ref "R54") (pin "A") (pinfunction "A_A") (pintype "passive"))
      (node (ref "R56") (pin "2") (pinfunction "2_2") (pintype "passive"))
    )
    (net (code "60") (name "Net-(IC2C-+IN)") (class "Default")
      (node (ref "IC2") (pin "10") (pinfunction "+IN_10") (pintype "input"))
      (node (ref "R61") (pin "1") (pinfunction "1_1") (pintype "passive"))
    )
    (net (code "61") (name "Net-(IC2C--IN)") (class "Default")
      (node (ref "C31") (pin "1") (pinfunction "1_1") (pintype "passive"))
      (node (ref "IC2") (pin "9") (pinfunction "-IN_9") (pintype "input"))
      (node (ref "R59") (pin "A") (pinfunction "A_A") (pintype "passive"))
    )
    (net (code "62") (name "Net-(IC2C-OUT)") (class "Default")
      (node (ref "C30") (pin "1") (pinfunction "1_1") (pintype "passive"))
      (node (ref "IC2") (pin "8") (pinfunction "OUT_8") (pintype "output"))
      (node (ref "R60") (pin "A") (pinfunction "A_A") (pintype "passive"))
      (node (ref "R62") (pin "2") (pinfunction "2_2") (pintype "passive"))
    )
    (net (code "63") (name "Net-(IC2D-+IN)") (class "Default")
      (node (ref "IC2") (pin "12") (pinfunction "+IN_12") (pintype "input"))
      (node (ref "R67") (pin "1") (pinfunction "1_1") (pintype "passive"))
    )
    (net (code "64") (name "Net-(IC2D--IN)") (class "Default")
      (node (ref "C34") (pin "1") (pinfunction "1_1") (pintype "passive"))
      (node (ref "IC2") (pin "13") (pinfunction "-IN_13") (pintype "input"))
      (node (ref "R65") (pin "A") (pinfunction "A_A") (pintype "passive"))
    )
    (net (code "65") (name "Net-(IC2D-OUT)") (class "Default")
      (node (ref "C33") (pin "1") (pinfunction "1_1") (pintype "passive"))
      (node (ref "IC2") (pin "14") (pinfunction "OUT_14") (pintype "output"))
      (node (ref "R66") (pin "A") (pinfunction "A_A") (pintype "passive"))
      (node (ref "R69B") (pin "2") (pinfunction "2_2") (pintype "passive"))
    )
    (net (code "66") (name "Net-(IC3A-+IN)") (class "Default")
      (node (ref "IC3") (pin "3") (pinfunction "+IN_3") (pintype "input"))
      (node (ref "R74") (pin "1") (pinfunction "1_1") (pintype "passive"))
    )
    (net (code "67") (name "Net-(IC3A--IN)") (class "Default")
      (node (ref "C38") (pin "2") (pinfunction "2_2") (pintype "passive"))
      (node (ref "IC3") (pin "2") (pinfunction "-IN_2") (pintype "input"))
      (node (ref "R72") (pin "1") (pinfunction "1_1") (pintype "passive"))
      (node (ref "R73") (pin "2") (pinfunction "2_2") (pintype "passive"))
    )
    (net (code "68") (name "Net-(IC3A-OUT)") (class "Default")
      (node (ref "C38") (pin "1") (pinfunction "1_1") (pintype "passive"))
      (node (ref "IC3") (pin "1") (pinfunction "OUT_1") (pintype "output"))
      (node (ref "R73") (pin "1") (pinfunction "1_1") (pintype "passive"))
      (node (ref "R75") (pin "2") (pinfunction "2_2") (pintype "passive"))
    )
    (net (code "69") (name "Net-(IC3B-+IN)") (class "Default")
      (node (ref "IC3") (pin "5") (pinfunction "+IN_5") (pintype "input"))
      (node (ref "R70") (pin "1") (pinfunction "1_1") (pintype "passive"))
    )
    (net (code "70") (name "Net-(IC3B-OUT)") (class "Default")
      (node (ref "C36") (pin "1") (pinfunction "1_1") (pintype "passive"))
      (node (ref "C37") (pin "2") (pinfunction "2_2") (pintype "passive"))
      (node (ref "IC3") (pin "7") (pinfunction "OUT_7") (pintype "output"))
      (node (ref "R71") (pin "1") (pinfunction "1_1") (pintype "passive"))
    )
    (net (code "71") (name "Net-(IC4A-+IN)") (class "Default")
      (node (ref "C22") (pin "1") (pinfunction "1_1") (pintype "passive"))
      (node (ref "IC4") (pin "3") (pinfunction "+IN_3") (pintype "input"))
      (node (ref "R40") (pin "1") (pinfunction "1_1") (pintype "passive"))
    )
    (net (code "72") (name "Net-(IC4A--IN)") (class "Default")
      (node (ref "C23") (pin "2") (pinfunction "2_2") (pintype "passive"))
      (node (ref "IC4") (pin "2") (pinfunction "-IN_2") (pintype "input"))
      (node (ref "R41") (pin "2") (pinfunction "2_2") (pintype "passive"))
    )
    (net (code "73") (name "Net-(IC4A-OUT)") (class "Default")
      (node (ref "C23") (pin "1") (pinfunction "1_1") (pintype "passive"))
      (node (ref "IC4") (pin "1") (pinfunction "OUT_1") (pintype "output"))
      (node (ref "R39") (pin "2") (pinfunction "2_2") (pintype "passive"))
      (node (ref "R41") (pin "1") (pinfunction "1_1") (pintype "passive"))
      (node (ref "R42") (pin "2") (pinfunction "2_2") (pintype "passive"))
    )
    (net (code "74") (name "Net-(IC4B-+IN)") (class "Default")
      (node (ref "C5") (pin "2") (pinfunction "2_2") (pintype "passive"))
      (node (ref "IC4") (pin "5") (pinfunction "+IN_5") (pintype "input"))
      (node (ref "R6") (pin "1") (pinfunction "1_1") (pintype "passive"))
    )
    (net (code "75") (name "Net-(IC4B--IN)") (class "Default")
      (node (ref "C6") (pin "2") (pinfunction "2_2") (pintype "passive"))
      (node (ref "IC4") (pin "6") (pinfunction "-IN_6") (pintype "input"))
      (node (ref "R7") (pin "2") (pinfunction "2_2") (pintype "passive"))
    )
    (net (code "76") (name "Net-(IC4B-OUT)") (class "Default")
      (node (ref "C4") (pin "1") (pinfunction "1_1") (pintype "passive"))
      (node (ref "C6") (pin "1") (pinfunction "1_1") (pintype "passive"))
      (node (ref "IC4") (pin "7") (pinfunction "OUT_7") (pintype "output"))
      (node (ref "R7") (pin "1") (pinfunction "1_1") (pintype "passive"))
      (node (ref "R8") (pin "2") (pinfunction "2_2") (pintype "passive"))
    )
    (net (code "77") (name "Net-(IC4C-+IN)") (class "Default")
      (node (ref "IC4") (pin "10") (pinfunction "+IN_10") (pintype "input"))
      (node (ref "R37") (pin "1") (pinfunction "1_1") (pintype "passive"))
    )
    (net (code "78") (name "Net-(IC4C--IN)") (class "Default")
      (node (ref "C19") (pin "2") (pinfunction "2_2") (pintype "passive"))
      (node (ref "IC4") (pin "9") (pinfunction "-IN_9") (pintype "input"))
      (node (ref "R35") (pin "1") (pinfunction "1_1") (pintype "passive"))
      (node (ref "R36") (pin "2") (pinfunction "2_2") (pintype "passive"))
    )
    (net (code "79") (name "Net-(IC4C-OUT)") (class "Default")
      (node (ref "C19") (pin "1") (pinfunction "1_1") (pintype "passive"))
      (node (ref "C20") (pin "2") (pinfunction "2_2") (pintype "passive"))
      (node (ref "IC4") (pin "8") (pinfunction "OUT_8") (pintype "output"))
      (node (ref "R36") (pin "1") (pinfunction "1_1") (pintype "passive"))
      (node (ref "R43") (pin "1") (pinfunction "1_1") (pintype "passive"))
    )
    (net (code "80") (name "Net-(IC4D-+IN)") (class "Default")
      (node (ref "IC4") (pin "12") (pinfunction "+IN_12") (pintype "input"))
      (node (ref "R3") (pin "1") (pinfunction "1_1") (pintype "passive"))
    )
    (net (code "81") (name "Net-(IC4D--IN)") (class "Default")
      (node (ref "C2") (pin "2") (pinfunction "2_2") (pintype "passive"))
      (node (ref "IC4") (pin "13") (pinfunction "-IN_13") (pintype "input"))
      (node (ref "R1") (pin "1") (pinfunction "1_1") (pintype "passive"))
      (node (ref "R2") (pin "2") (pinfunction "2_2") (pintype "passive"))
    )
    (net (code "82") (name "Net-(IC4D-OUT)") (class "Default")
      (node (ref "C2") (pin "1") (pinfunction "1_1") (pintype "passive"))
      (node (ref "IC4") (pin "14") (pinfunction "OUT_14") (pintype "output"))
      (node (ref "R2") (pin "1") (pinfunction "1_1") (pintype "passive"))
      (node (ref "R35") (pin "2") (pinfunction "2_2") (pintype "passive"))
      (node (ref "R4") (pin "2") (pinfunction "2_2") (pintype "passive"))
      (node (ref "R9") (pin "1") (pinfunction "1_1") (pintype "passive"))
    )
    (net (code "83") (name "Net-(R11-Pad1)") (class "Default")
      (node (ref "R11") (pin "1") (pinfunction "1_1") (pintype "passive"))
      (node (ref "R12") (pin "S") (pinfunction "S_S") (pintype "passive"))
    )
    (net (code "84") (name "Net-(R18-Pad1)") (class "Default")
      (node (ref "R18") (pin "1") (pinfunction "1_1") (pintype "passive"))
      (node (ref "R19") (pin "S") (pinfunction "S_S") (pintype "passive"))
    )
    (net (code "85") (name "Net-(R24-Pad1)") (class "Default")
      (node (ref "R24") (pin "1") (pinfunction "1_1") (pintype "passive"))
      (node (ref "R25") (pin "S") (pinfunction "S_S") (pintype "passive"))
    )
    (net (code "86") (name "Net-(R30-Pad1)") (class "Default")
      (node (ref "R30") (pin "1") (pinfunction "1_1") (pintype "passive"))
      (node (ref "R31") (pin "S") (pinfunction "S_S") (pintype "passive"))
    )
    (net (code "87") (name "Net-(R45-Pad1)") (class "Default")
      (node (ref "R45") (pin "1") (pinfunction "1_1") (pintype "passive"))
      (node (ref "R46") (pin "S") (pinfunction "S_S") (pintype "passive"))
    )
    (net (code "88") (name "Net-(R52-Pad1)") (class "Default")
      (node (ref "R52") (pin "1") (pinfunction "1_1") (pintype "passive"))
      (node (ref "R53") (pin "S") (pinfunction "S_S") (pintype "passive"))
    )
    (net (code "89") (name "Net-(R58-Pad1)") (class "Default")
      (node (ref "R58") (pin "1") (pinfunction "1_1") (pintype "passive"))
      (node (ref "R59") (pin "S") (pinfunction "S_S") (pintype "passive"))
    )
    (net (code "90") (name "Net-(R64-Pad1)") (class "Default")
      (node (ref "R64") (pin "1") (pinfunction "1_1") (pintype "passive"))
      (node (ref "R65") (pin "S") (pinfunction "S_S") (pintype "passive"))
    )
    (net (code "91") (name "Net-(R75-Pad1)") (class "Default")
      (node (ref "R75") (pin "1") (pinfunction "1_1") (pintype "passive"))
      (node (ref "SUMOUT") (pin "SIGNAL") (pinfunction "SIGNAL_SIGNAL") (pintype "passive"))
    )
    (net (code "92") (name "Net-(R76-PadS)") (class "Default")
      (node (ref "R76") (pin "S") (pinfunction "S_S") (pintype "passive"))
      (node (ref "R77") (pin "1") (pinfunction "1_1") (pintype "passive"))
    )
    (net (code "93") (name "Net-(R78-PadS)") (class "Default")
      (node (ref "R78") (pin "S") (pinfunction "S_S") (pintype "passive"))
      (node (ref "R79") (pin "1") (pinfunction "1_1") (pintype "passive"))
    )
    (net (code "94") (name "Net-(R80-PadS)") (class "Default")
      (node (ref "R80") (pin "S") (pinfunction "S_S") (pintype "passive"))
      (node (ref "R81") (pin "1") (pinfunction "1_1") (pintype "passive"))
    )
    (net (code "95") (name "Net-(R82-PadS)") (class "Default")
      (node (ref "R82") (pin "S") (pinfunction "S_S") (pintype "passive"))
      (node (ref "R83") (pin "1") (pinfunction "1_1") (pintype "passive"))
    )
    (net (code "96") (name "Net-(R84-PadS)") (class "Default")
      (node (ref "R84") (pin "S") (pinfunction "S_S") (pintype "passive"))
      (node (ref "R85") (pin "1") (pinfunction "1_1") (pintype "passive"))
    )
    (net (code "97") (name "Net-(R86-PadS)") (class "Default")
      (node (ref "R86") (pin "S") (pinfunction "S_S") (pintype "passive"))
      (node (ref "R87") (pin "1") (pinfunction "1_1") (pintype "passive"))
    )
    (net (code "98") (name "Net-(R88-PadS)") (class "Default")
      (node (ref "R88") (pin "S") (pinfunction "S_S") (pintype "passive"))
      (node (ref "R89") (pin "1") (pinfunction "1_1") (pintype "passive"))
    )
    (net (code "99") (name "Net-(R90-PadS)") (class "Default")
      (node (ref "R90") (pin "S") (pinfunction "S_S") (pintype "passive"))
      (node (ref "R91") (pin "1") (pinfunction "1_1") (pintype "passive"))
    )
    (net (code "100") (name "Net-(R92-PadS)") (class "Default")
      (node (ref "R92") (pin "S") (pinfunction "S_S") (pintype "passive"))
      (node (ref "R93") (pin "1") (pinfunction "1_1") (pintype "passive"))
    )
    (net (code "101") (name "Net-(R94-PadS)") (class "Default")
      (node (ref "R94") (pin "S") (pinfunction "S_S") (pintype "passive"))
      (node (ref "R95") (pin "1") (pinfunction "1_1") (pintype "passive"))
    )
    (net (code "102") (name "V+") (class "Default")
      (node (ref "C101") (pin "+") (pinfunction "+_+") (pintype "passive"))
      (node (ref "C103") (pin "1") (pinfunction "1_1") (pintype "passive"))
      (node (ref "C105") (pin "1") (pinfunction "1_1") (pintype "passive"))
      (node (ref "C107") (pin "1") (pinfunction "1_1") (pintype "passive"))
      (node (ref "C109") (pin "1") (pinfunction "1_1") (pintype "passive"))
      (node (ref "L1") (pin "2") (pinfunction "2_2") (pintype "passive"))
    )
    (net (code "103") (name "V-") (class "Default")
      (node (ref "C102") (pin "-") (pinfunction "-_-") (pintype "passive"))
      (node (ref "C104") (pin "2") (pinfunction "2_2") (pintype "passive"))
      (node (ref "C106") (pin "2") (pinfunction "2_2") (pintype "passive"))
      (node (ref "C108") (pin "2") (pinfunction "2_2") (pintype "passive"))
      (node (ref "C110") (pin "2") (pinfunction "2_2") (pintype "passive"))
      (node (ref "L2") (pin "2") (pinfunction "2_2") (pintype "passive"))
    )
    (net (code "104") (name "unconnected-(R12-PadE)") (class "Default")
      (node (ref "R12") (pin "E") (pinfunction "E_E") (pintype "passive"))
    )
    (net (code "105") (name "unconnected-(R19-PadE)") (class "Default")
      (node (ref "R19") (pin "E") (pinfunction "E_E") (pintype "passive"))
    )
    (net (code "106") (name "unconnected-(R25-PadE)") (class "Default")
      (node (ref "R25") (pin "E") (pinfunction "E_E") (pintype "passive"))
    )
    (net (code "107") (name "unconnected-(R31-PadE)") (class "Default")
      (node (ref "R31") (pin "E") (pinfunction "E_E") (pintype "passive"))
    )
    (net (code "108") (name "unconnected-(R46-PadE)") (class "Default")
      (node (ref "R46") (pin "E") (pinfunction "E_E") (pintype "passive"))
    )
    (net (code "109") (name "unconnected-(R53-PadE)") (class "Default")
      (node (ref "R53") (pin "E") (pinfunction "E_E") (pintype "passive"))
    )
    (net (code "110") (name "unconnected-(R59-PadE)") (class "Default")
      (node (ref "R59") (pin "E") (pinfunction "E_E") (pintype "passive"))
    )
    (net (code "111") (name "unconnected-(R65-PadE)") (class "Default")
      (node (ref "R65") (pin "E") (pinfunction "E_E") (pintype "passive"))
    )
  )
)
